# rxcalibrate.net
KiCad netlist of a schematic drawn in Altium Designer
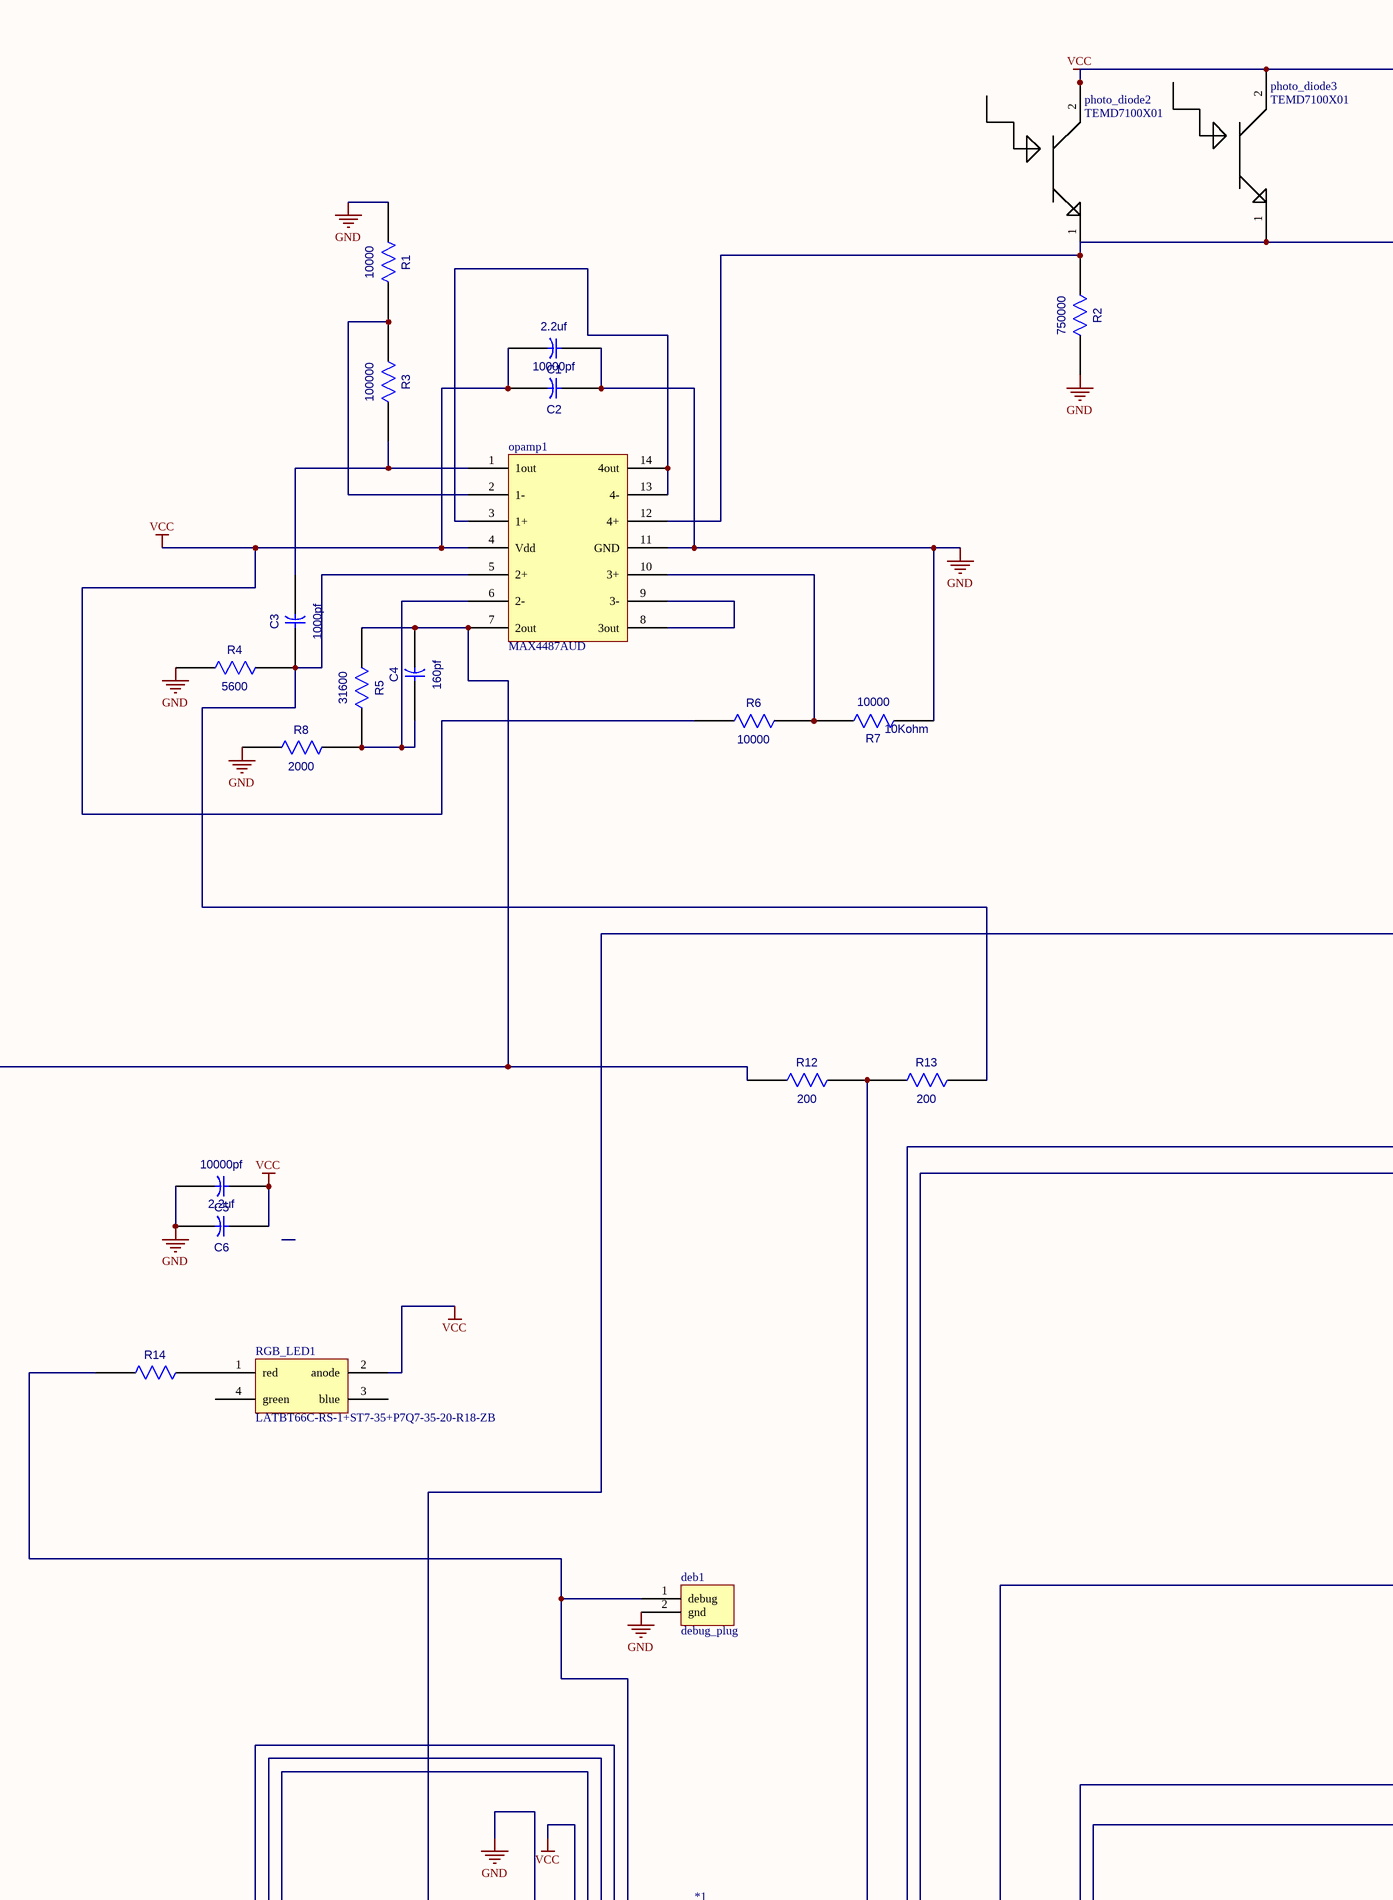
[diagram p0: rxcalibrate.SchDoc, top left]
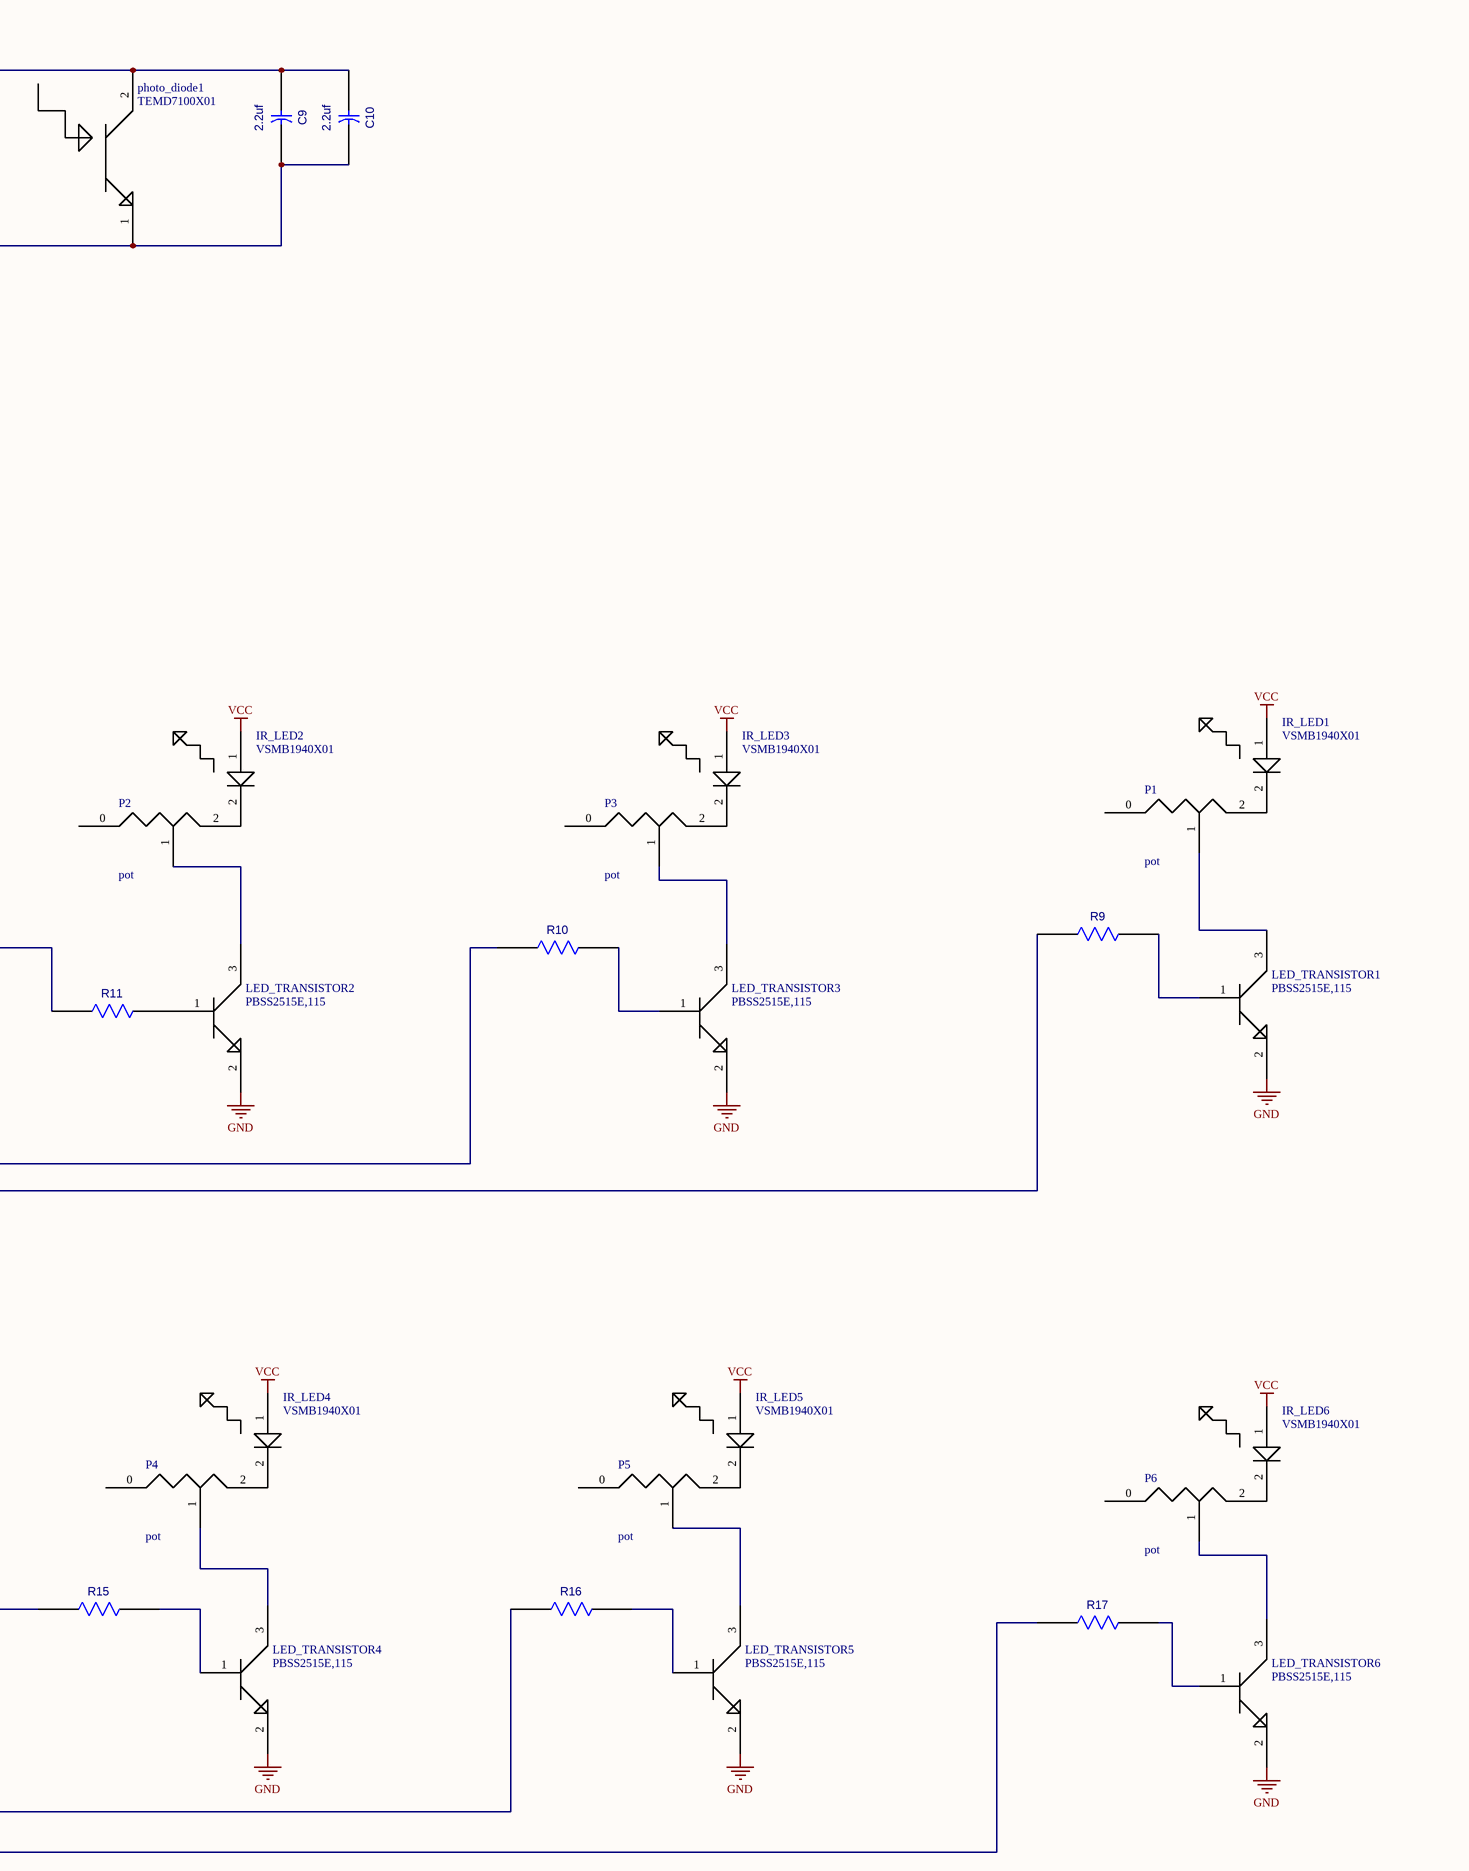
[diagram p1: rxcalibrate.SchDoc, top right]
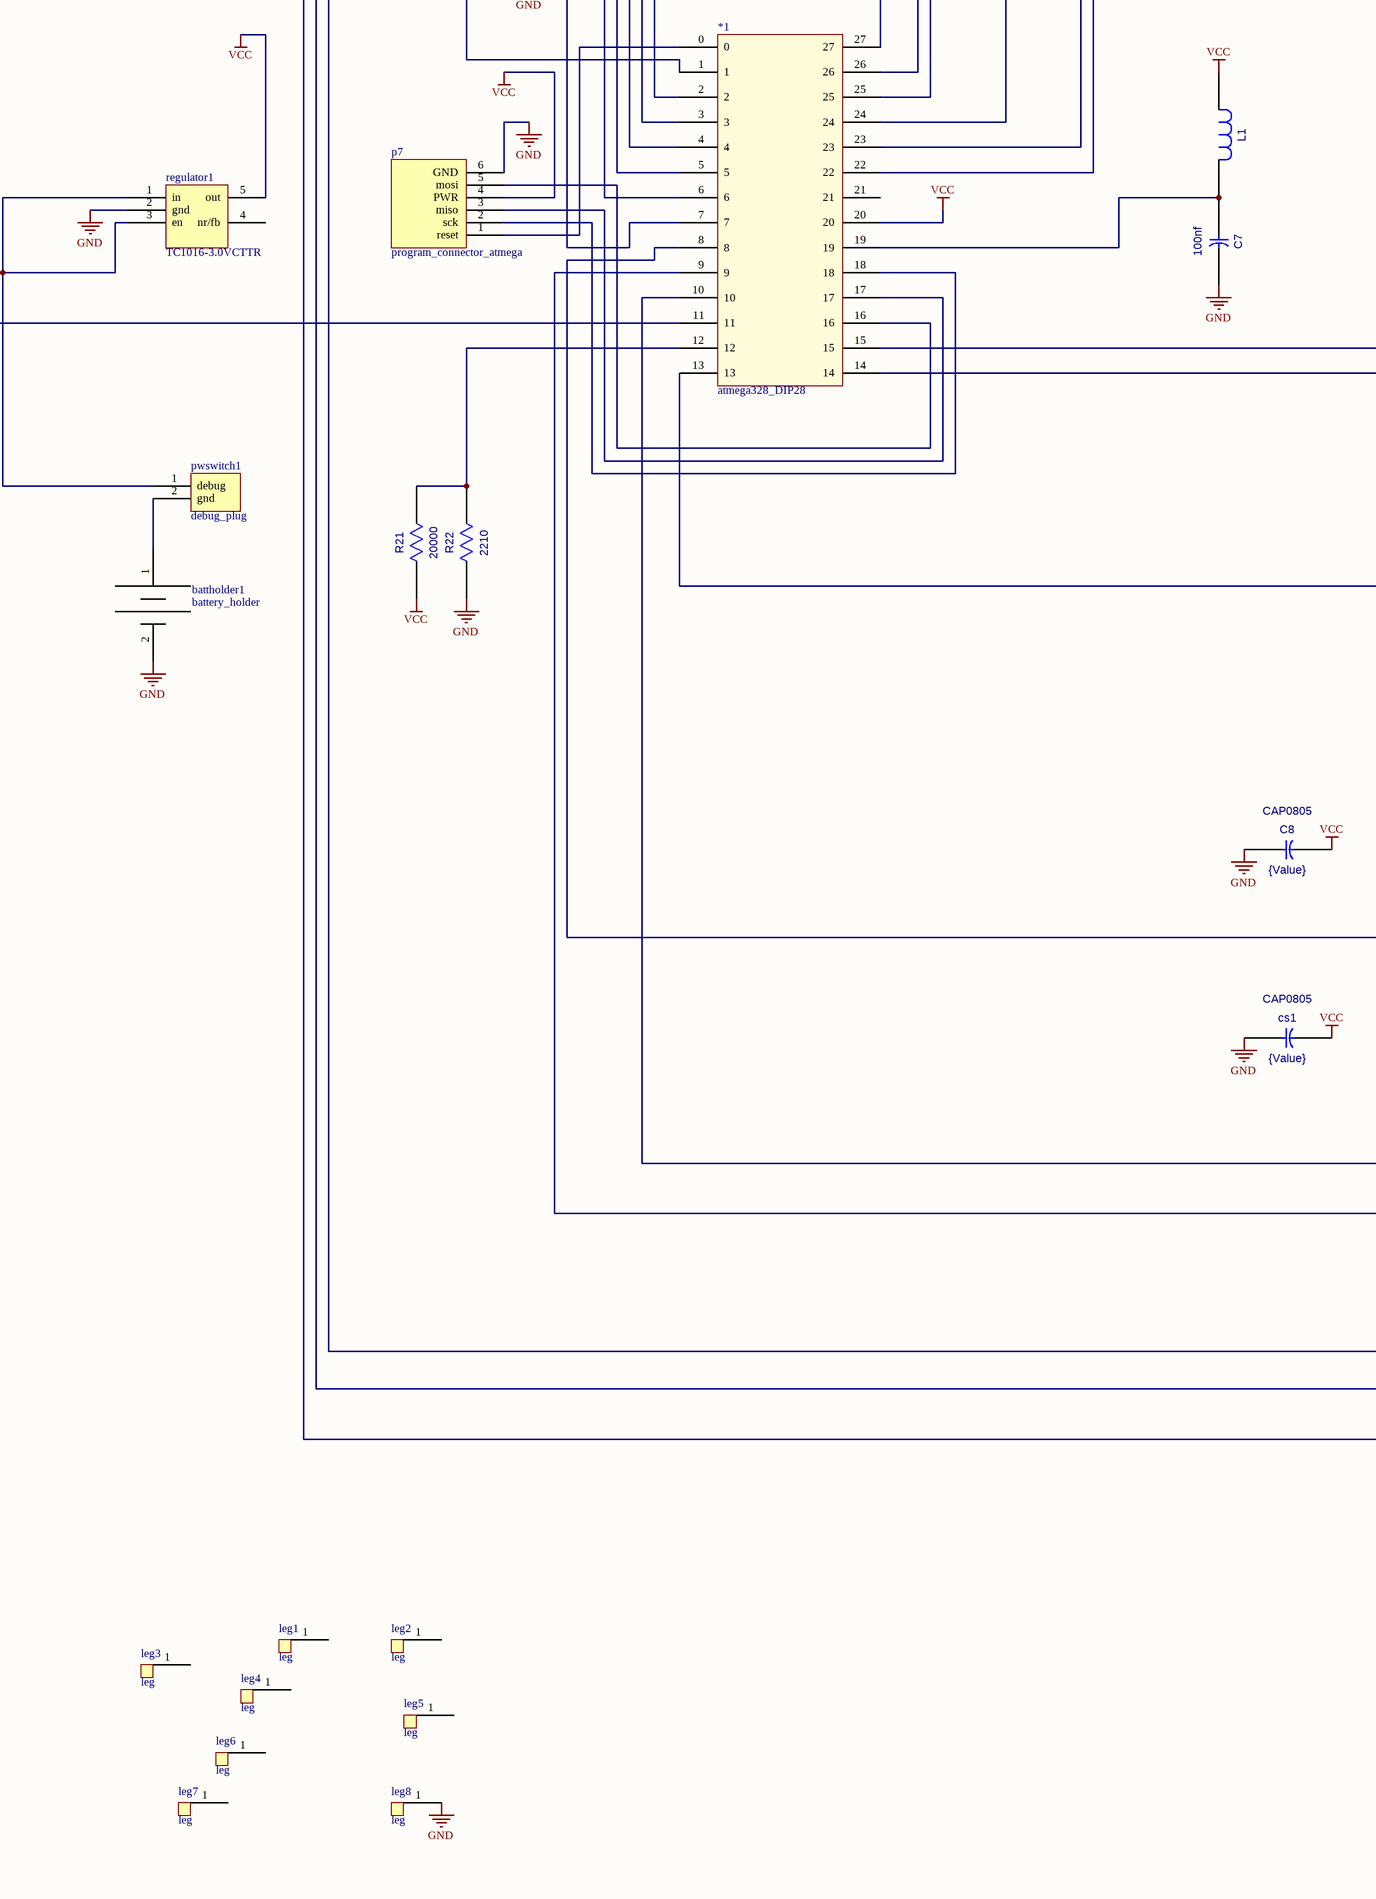
[diagram p2: rxcalibrate.SchDoc, bottom left]
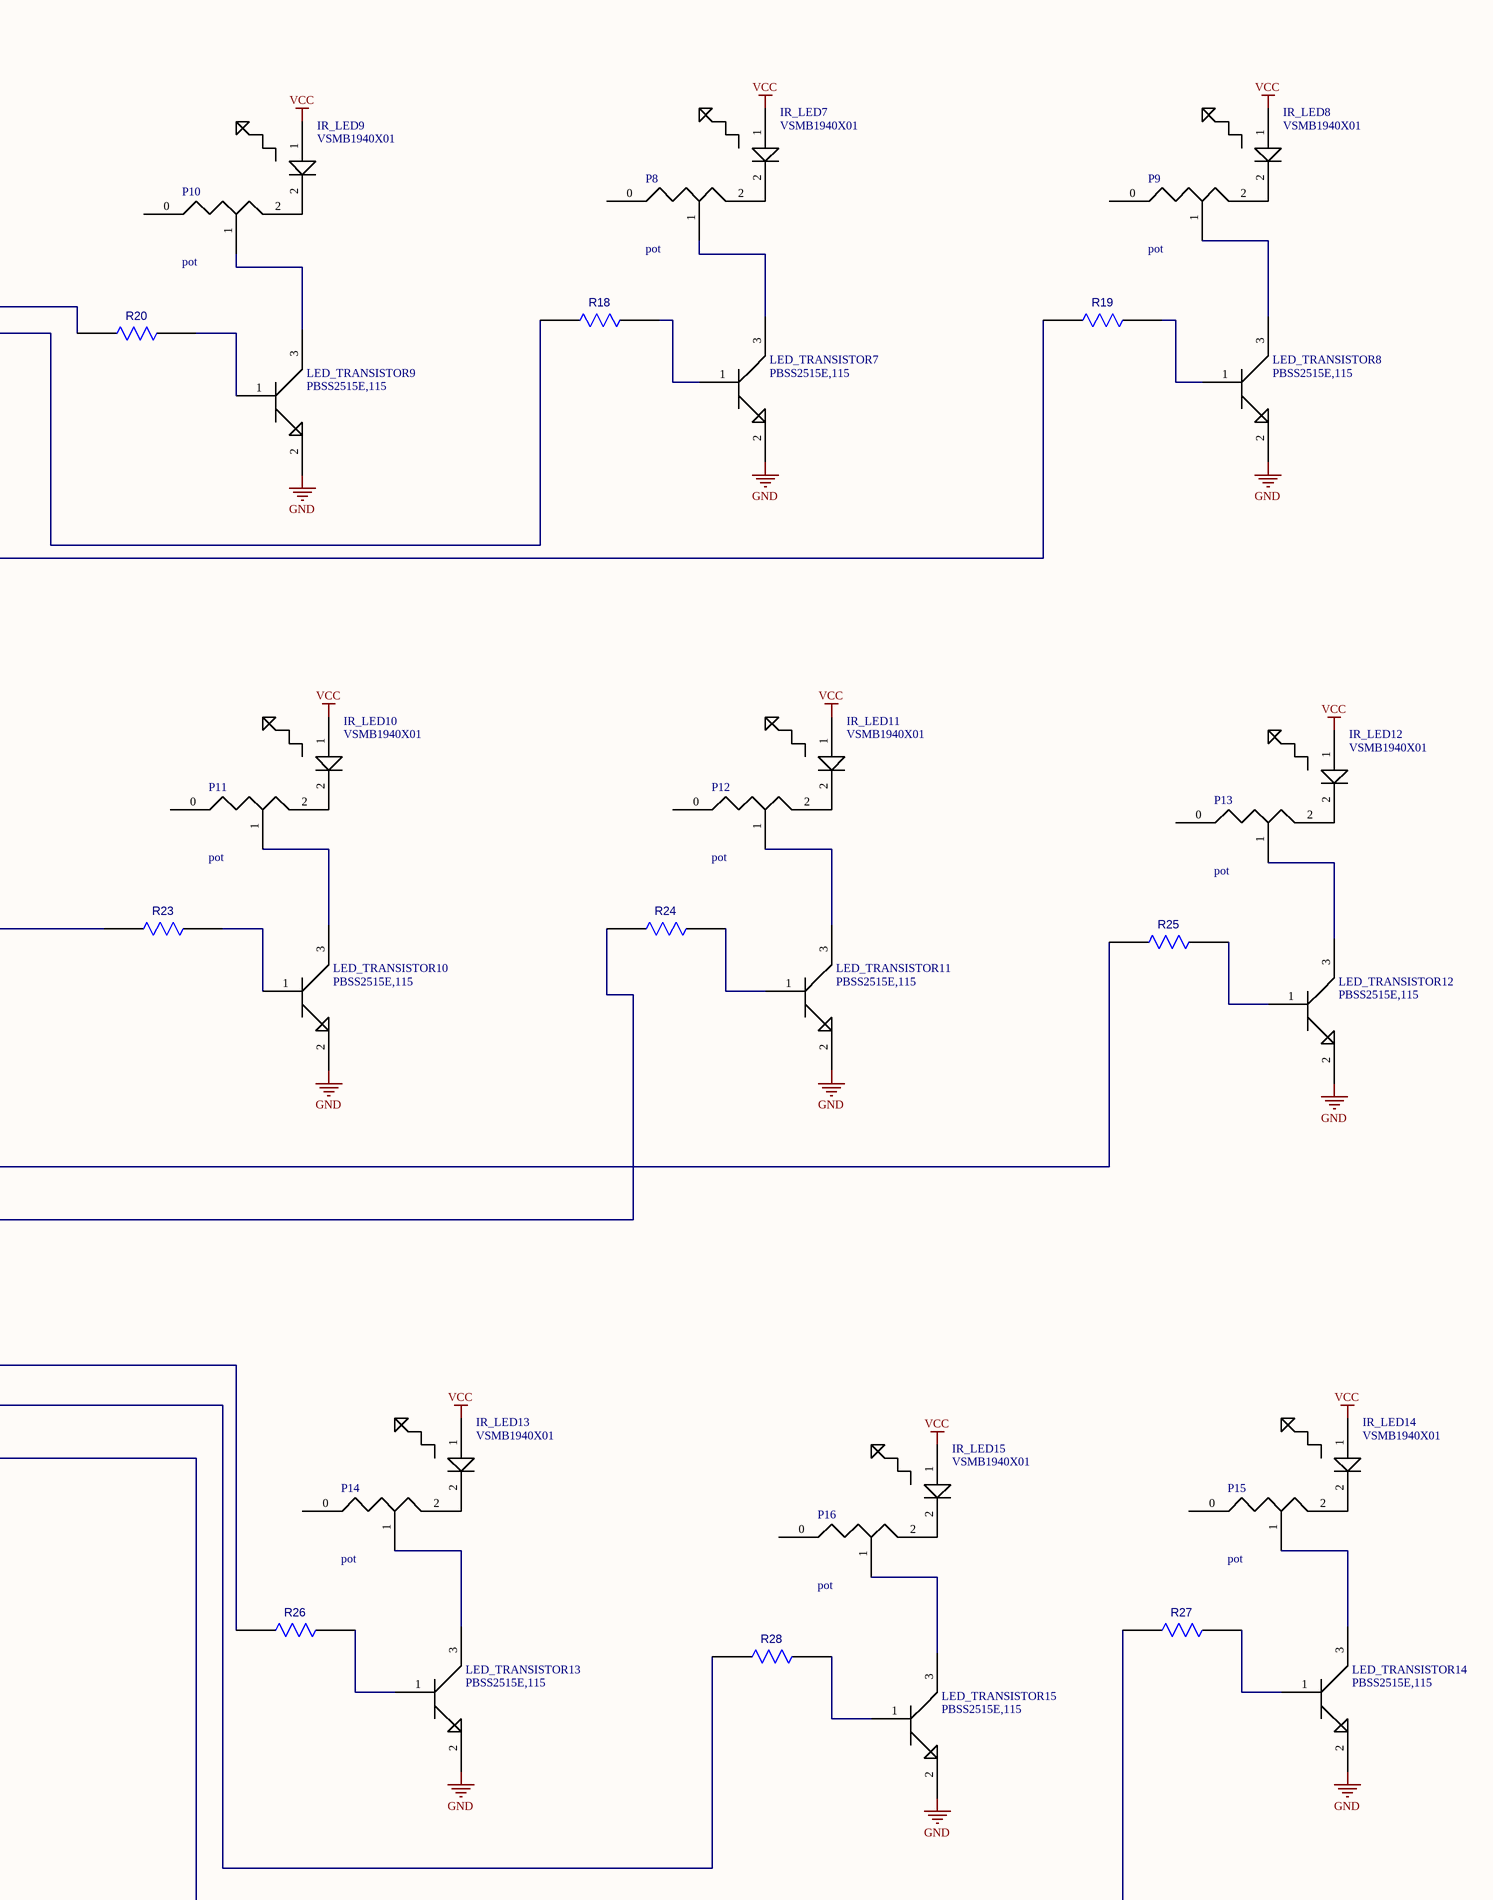
[diagram p3: rxcalibrate.SchDoc, bottom right]

(export (version "E")
  (design (tool "Eeschema 10.0.6"))
  (components
    (comp (ref "*1")
      (value "atmega328_DIP28")
      (footprint "atmega328dip")
      (libsource (lib "JMAC.~(21)") (part "atmega328_DIP28"))
    )
    (comp (ref "battholder1")
      (value "battery_holder")
      (footprint "Battery_mount")
      (libsource (lib "JMAC.~(21)") (part "battery_holder"))
    )
    (comp (ref "C1")
      (value "2.2uf")
      (footprint "RC0603")
      (description "CAP0603")
      (fields (field (name "ALTIUM_UNNAMED_1") "2.2uf"))
      (libsource (lib "JMAC") (part "CAP0603"))
    )
    (comp (ref "C2")
      (value "10000pf")
      (footprint "RC0603")
      (description "CAP0603")
      (fields (field (name "ALTIUM_UNNAMED_1") "10000pf"))
      (libsource (lib "JMAC") (part "CAP0603"))
    )
    (comp (ref "C3")
      (value "1000pf")
      (footprint "RC0603")
      (description "CAP0603")
      (fields (field (name "ALTIUM_UNNAMED_1") "1000pf"))
      (libsource (lib "JMAC") (part "CAP0603"))
    )
    (comp (ref "C4")
      (value "160pf")
      (footprint "RC0603")
      (description "CAP0603")
      (fields (field (name "ALTIUM_UNNAMED_1") "160pf"))
      (libsource (lib "JMAC") (part "CAP0603"))
    )
    (comp (ref "C5")
      (value "10000pf")
      (footprint "RC0603")
      (description "CAP0603")
      (fields (field (name "ALTIUM_UNNAMED_1") "10000pf"))
      (libsource (lib "JMAC") (part "CAP0603"))
    )
    (comp (ref "C6")
      (value "2.2uf")
      (footprint "RC0603")
      (description "CAP0603")
      (fields (field (name "ALTIUM_UNNAMED_1") "2.2uf"))
      (libsource (lib "JMAC") (part "CAP0603"))
    )
    (comp (ref "C7")
      (value "100nf")
      (footprint "RC0603")
      (description "CAP0603")
      (fields (field (name "ALTIUM_UNNAMED_1") "100nf"))
      (libsource (lib "JMAC") (part "CAP0603"))
    )
    (comp (ref "C8")
      (value "CAP0805")
      (footprint "RC0805_CAP0805(Primary)")
      (fields (field (name "ALTIUM_VALUE") "{Value}"))
      (libsource (lib "JMAC.~(21)") (part "CAP0805"))
    )
    (comp (ref "C9")
      (value "2.2uf")
      (footprint "RC0603")
      (description "CAP0603")
      (fields (field (name "ALTIUM_UNNAMED_1") "2.2uf"))
      (libsource (lib "JMAC") (part "CAP0603"))
    )
    (comp (ref "C10")
      (value "2.2uf")
      (footprint "RC0603")
      (description "CAP0603")
      (fields (field (name "ALTIUM_UNNAMED_1") "2.2uf"))
      (libsource (lib "JMAC") (part "CAP0603"))
    )
    (comp (ref "cs1")
      (value "CAP0805")
      (footprint "RC0805_CAP0805(Primary)")
      (fields (field (name "ALTIUM_VALUE") "{Value}"))
      (libsource (lib "JMAC.~(21)") (part "CAP0805"))
    )
    (comp (ref "deb1")
      (value "debug_plug")
      (footprint "debug_conn")
      (libsource (lib "JMAC.~(21)") (part "debug_plug"))
    )
    (comp (ref "IR_LED1")
      (value "VSMB1940X01")
      (footprint "0805")
      (libsource (lib "JMAC.~(21)") (part "IRtx"))
    )
    (comp (ref "IR_LED2")
      (value "VSMB1940X01")
      (footprint "0805")
      (libsource (lib "JMAC.~(21)") (part "IRtx"))
    )
    (comp (ref "IR_LED3")
      (value "VSMB1940X01")
      (footprint "0805")
      (libsource (lib "JMAC.~(21)") (part "IRtx"))
    )
    (comp (ref "IR_LED4")
      (value "VSMB1940X01")
      (footprint "0805")
      (libsource (lib "JMAC.~(21)") (part "IRtx"))
    )
    (comp (ref "IR_LED5")
      (value "VSMB1940X01")
      (footprint "0805")
      (libsource (lib "JMAC.~(21)") (part "IRtx"))
    )
    (comp (ref "IR_LED6")
      (value "VSMB1940X01")
      (footprint "0805")
      (libsource (lib "JMAC.~(21)") (part "IRtx"))
    )
    (comp (ref "IR_LED7")
      (value "VSMB1940X01")
      (footprint "0805")
      (libsource (lib "JMAC.~(21)") (part "IRtx"))
    )
    (comp (ref "IR_LED8")
      (value "VSMB1940X01")
      (footprint "0805")
      (libsource (lib "JMAC.~(21)") (part "IRtx"))
    )
    (comp (ref "IR_LED9")
      (value "VSMB1940X01")
      (footprint "0805")
      (libsource (lib "JMAC.~(21)") (part "IRtx"))
    )
    (comp (ref "IR_LED10")
      (value "VSMB1940X01")
      (footprint "0805")
      (libsource (lib "JMAC.~(21)") (part "IRtx"))
    )
    (comp (ref "IR_LED11")
      (value "VSMB1940X01")
      (footprint "0805")
      (libsource (lib "JMAC.~(21)") (part "IRtx"))
    )
    (comp (ref "IR_LED12")
      (value "VSMB1940X01")
      (footprint "0805")
      (libsource (lib "JMAC.~(21)") (part "IRtx"))
    )
    (comp (ref "IR_LED13")
      (value "VSMB1940X01")
      (footprint "0805")
      (libsource (lib "JMAC.~(21)") (part "IRtx"))
    )
    (comp (ref "IR_LED14")
      (value "VSMB1940X01")
      (footprint "0805")
      (libsource (lib "JMAC.~(21)") (part "IRtx"))
    )
    (comp (ref "IR_LED15")
      (value "VSMB1940X01")
      (footprint "0805")
      (libsource (lib "JMAC.~(21)") (part "IRtx"))
    )
    (comp (ref "L1")
      (value "LQM18FN100M00D")
      (footprint "RC0603")
      (description "IND0603")
      (libsource (lib "JMAC.~(21)") (part "IND0603"))
    )
    (comp (ref "LED_TRANSISTOR1")
      (value "PBSS2515E,115")
      (footprint "sot416")
      (libsource (lib "JMAC.~(21)") (part "transistor_led"))
    )
    (comp (ref "LED_TRANSISTOR2")
      (value "PBSS2515E,115")
      (footprint "sot416")
      (libsource (lib "JMAC.~(21)") (part "transistor_led"))
    )
    (comp (ref "LED_TRANSISTOR3")
      (value "PBSS2515E,115")
      (footprint "sot416")
      (libsource (lib "JMAC.~(21)") (part "transistor_led"))
    )
    (comp (ref "LED_TRANSISTOR4")
      (value "PBSS2515E,115")
      (footprint "sot416")
      (libsource (lib "JMAC.~(21)") (part "transistor_led"))
    )
    (comp (ref "LED_TRANSISTOR5")
      (value "PBSS2515E,115")
      (footprint "sot416")
      (libsource (lib "JMAC.~(21)") (part "transistor_led"))
    )
    (comp (ref "LED_TRANSISTOR6")
      (value "PBSS2515E,115")
      (footprint "sot416")
      (libsource (lib "JMAC.~(21)") (part "transistor_led"))
    )
    (comp (ref "LED_TRANSISTOR7")
      (value "PBSS2515E,115")
      (footprint "sot416")
      (libsource (lib "JMAC.~(21)") (part "transistor_led"))
    )
    (comp (ref "LED_TRANSISTOR8")
      (value "PBSS2515E,115")
      (footprint "sot416")
      (libsource (lib "JMAC.~(21)") (part "transistor_led"))
    )
    (comp (ref "LED_TRANSISTOR9")
      (value "PBSS2515E,115")
      (footprint "sot416")
      (libsource (lib "JMAC.~(21)") (part "transistor_led"))
    )
    (comp (ref "LED_TRANSISTOR10")
      (value "PBSS2515E,115")
      (footprint "sot416")
      (libsource (lib "JMAC.~(21)") (part "transistor_led"))
    )
    (comp (ref "LED_TRANSISTOR11")
      (value "PBSS2515E,115")
      (footprint "sot416")
      (libsource (lib "JMAC.~(21)") (part "transistor_led"))
    )
    (comp (ref "LED_TRANSISTOR12")
      (value "PBSS2515E,115")
      (footprint "sot416")
      (libsource (lib "JMAC.~(21)") (part "transistor_led"))
    )
    (comp (ref "LED_TRANSISTOR13")
      (value "PBSS2515E,115")
      (footprint "sot416")
      (libsource (lib "JMAC.~(21)") (part "transistor_led"))
    )
    (comp (ref "LED_TRANSISTOR14")
      (value "PBSS2515E,115")
      (footprint "sot416")
      (libsource (lib "JMAC.~(21)") (part "transistor_led"))
    )
    (comp (ref "LED_TRANSISTOR15")
      (value "PBSS2515E,115")
      (footprint "sot416")
      (libsource (lib "JMAC.~(21)") (part "transistor_led"))
    )
    (comp (ref "leg1") (value "leg") (footprint "leg") (libsource (lib "JMAC.~(21)") (part "leg")))
    (comp (ref "leg2") (value "leg") (footprint "leg") (libsource (lib "JMAC.~(21)") (part "leg")))
    (comp (ref "leg3") (value "leg") (footprint "leg") (libsource (lib "JMAC.~(21)") (part "leg")))
    (comp (ref "leg4") (value "leg") (footprint "leg") (libsource (lib "JMAC.~(21)") (part "leg")))
    (comp (ref "leg5") (value "leg") (footprint "leg") (libsource (lib "JMAC.~(21)") (part "leg")))
    (comp (ref "leg6") (value "leg") (footprint "leg") (libsource (lib "JMAC.~(21)") (part "leg")))
    (comp (ref "leg7") (value "leg") (footprint "leg") (libsource (lib "JMAC.~(21)") (part "leg")))
    (comp (ref "leg8") (value "leg") (footprint "leg") (libsource (lib "JMAC.~(21)") (part "leg")))
    (comp (ref "opamp1")
      (value "MAX4487AUD")
      (footprint "TSSOP14")
      (libsource (lib "JMAC.~(21)") (part "opamp"))
    )
    (comp (ref "P1") (value "pot") (footprint "POT_PV36W") (libsource (lib "JMAC.~(21)") (part "pot")))
    (comp (ref "P2") (value "pot") (footprint "POT_PV36W") (libsource (lib "JMAC.~(21)") (part "pot")))
    (comp (ref "P3") (value "pot") (footprint "POT_PV36W") (libsource (lib "JMAC.~(21)") (part "pot")))
    (comp (ref "P4") (value "pot") (footprint "POT_PV36W") (libsource (lib "JMAC.~(21)") (part "pot")))
    (comp (ref "P5") (value "pot") (footprint "POT_PV36W") (libsource (lib "JMAC.~(21)") (part "pot")))
    (comp (ref "P6") (value "pot") (footprint "POT_PV36W") (libsource (lib "JMAC.~(21)") (part "pot")))
    (comp (ref "p7")
      (value "program_connector_atmega")
      (footprint "Programming_connector")
      (libsource (lib "JMAC.~(21)") (part "program_connector_atmega"))
    )
    (comp (ref "P8") (value "pot") (footprint "POT_PV36W") (libsource (lib "JMAC.~(21)") (part "pot")))
    (comp (ref "P9") (value "pot") (footprint "POT_PV36W") (libsource (lib "JMAC.~(21)") (part "pot")))
    (comp (ref "P10") (value "pot") (footprint "POT_PV36W") (libsource (lib "JMAC.~(21)") (part "pot")))
    (comp (ref "P11") (value "pot") (footprint "POT_PV36W") (libsource (lib "JMAC.~(21)") (part "pot")))
    (comp (ref "P12") (value "pot") (footprint "POT_PV36W") (libsource (lib "JMAC.~(21)") (part "pot")))
    (comp (ref "P13") (value "pot") (footprint "POT_PV36W") (libsource (lib "JMAC.~(21)") (part "pot")))
    (comp (ref "P14") (value "pot") (footprint "POT_PV36W") (libsource (lib "JMAC.~(21)") (part "pot")))
    (comp (ref "P15") (value "pot") (footprint "POT_PV36W") (libsource (lib "JMAC.~(21)") (part "pot")))
    (comp (ref "P16") (value "pot") (footprint "POT_PV36W") (libsource (lib "JMAC.~(21)") (part "pot")))
    (comp (ref "photo_diode1")
      (value "TEMD7100X01")
      (footprint "0805")
      (libsource (lib "JMAC.~(21)") (part "IRrx"))
    )
    (comp (ref "photo_diode2")
      (value "TEMD7100X01")
      (footprint "0805")
      (libsource (lib "JMAC.~(21)") (part "IRrx"))
    )
    (comp (ref "photo_diode3")
      (value "TEMD7100X01")
      (footprint "0805")
      (libsource (lib "JMAC.~(21)") (part "IRrx"))
    )
    (comp (ref "pwswitch1")
      (value "debug_plug")
      (footprint "debug_conn")
      (libsource (lib "JMAC.~(21)") (part "debug_plug"))
    )
    (comp (ref "R1")
      (value "10 Kohm")
      (footprint "RC0603")
      (description "RES0603 10Kohm")
      (fields (field (name "ALTIUM_UNNAMED_1") "10000"))
      (libsource (lib "JMAC") (part "RES0603"))
    )
    (comp (ref "R2")
      (value "750 K ohm")
      (footprint "RC0603")
      (description "RES0603 750000 ohm")
      (fields (field (name "ALTIUM_UNNAMED_1") "750000"))
      (libsource (lib "JMAC") (part "RES0603"))
    )
    (comp (ref "R3")
      (value "100Kohm")
      (footprint "RC0603")
      (description "RES0603 100Kohm")
      (fields (field (name "ALTIUM_UNNAMED_1") "100000"))
      (libsource (lib "JMAC") (part "RES0603"))
    )
    (comp (ref "R4")
      (value "5600 ohm")
      (footprint "RC0603")
      (description "RES0603 5600 ohm")
      (fields (field (name "ALTIUM_UNNAMED_1") "5600"))
      (libsource (lib "JMAC") (part "RES0603"))
    )
    (comp (ref "R5")
      (value "31.6Kohm")
      (footprint "RC0603")
      (description "RES0603 31.6Kohm")
      (fields (field (name "ALTIUM_UNNAMED_1") "31600"))
      (libsource (lib "JMAC") (part "RES0603"))
    )
    (comp (ref "R6")
      (value "10Kohm")
      (footprint "RC0603")
      (description "RES0603 10Kohm")
      (fields (field (name "ALTIUM_UNNAMED_1") "10000"))
      (libsource (lib "JMAC") (part "RES0603"))
    )
    (comp (ref "R7")
      (value "10Kohm")
      (footprint "RC0603")
      (description "RES0603 10Kohm")
      (fields (field (name "ALTIUM_UNNAMED_1") "10000"))
      (libsource (lib "JMAC") (part "RES0603"))
    )
    (comp (ref "R8")
      (value "2Kohm")
      (footprint "RC0603")
      (description "RES0603 2Kohm")
      (fields (field (name "ALTIUM_UNNAMED_1") "2000"))
      (libsource (lib "JMAC") (part "RES0603"))
    )
    (comp (ref "R9") (value "RES0603") (footprint "RC0603") (libsource (lib "JMAC.~(21)") (part "RES0603")))
    (comp (ref "R10") (value "RES0603") (footprint "RC0603") (libsource (lib "JMAC.~(21)") (part "RES0603")))
    (comp (ref "R11") (value "RES0603") (footprint "RC0603") (libsource (lib "JMAC.~(21)") (part "RES0603")))
    (comp (ref "R12")
      (value "200 ohm")
      (footprint "RC0603")
      (description "RES0603 200 ohm")
      (fields (field (name "ALTIUM_UNNAMED_1") "200"))
      (libsource (lib "JMAC") (part "RES0603"))
    )
    (comp (ref "R13")
      (value "200 ohm")
      (footprint "RC0603")
      (description "RES0603 200 ohm")
      (fields (field (name "ALTIUM_UNNAMED_1") "200"))
      (libsource (lib "JMAC") (part "RES0603"))
    )
    (comp (ref "R14") (value "RES0603") (footprint "RC0603") (libsource (lib "JMAC.~(21)") (part "RES0603")))
    (comp (ref "R15") (value "RES0603") (footprint "RC0603") (libsource (lib "JMAC.~(21)") (part "RES0603")))
    (comp (ref "R16") (value "RES0603") (footprint "RC0603") (libsource (lib "JMAC.~(21)") (part "RES0603")))
    (comp (ref "R17") (value "RES0603") (footprint "RC0603") (libsource (lib "JMAC.~(21)") (part "RES0603")))
    (comp (ref "R18") (value "RES0603") (footprint "RC0603") (libsource (lib "JMAC.~(21)") (part "RES0603")))
    (comp (ref "R19") (value "RES0603") (footprint "RC0603") (libsource (lib "JMAC.~(21)") (part "RES0603")))
    (comp (ref "R20") (value "RES0603") (footprint "RC0603") (libsource (lib "JMAC.~(21)") (part "RES0603")))
    (comp (ref "R21")
      (value "20Kohm")
      (footprint "RC0603")
      (description "RES0603 20Kohm")
      (fields (field (name "ALTIUM_UNNAMED_1") "20000"))
      (libsource (lib "JMAC") (part "RES0603"))
    )
    (comp (ref "R22")
      (value "2210 ohm")
      (footprint "RC0603")
      (description "RES0603 2210 ohm")
      (fields (field (name "ALTIUM_UNNAMED_1") "2210"))
      (libsource (lib "JMAC") (part "RES0603"))
    )
    (comp (ref "R23") (value "RES0603") (footprint "RC0603") (libsource (lib "JMAC.~(21)") (part "RES0603")))
    (comp (ref "R24") (value "RES0603") (footprint "RC0603") (libsource (lib "JMAC.~(21)") (part "RES0603")))
    (comp (ref "R25") (value "RES0603") (footprint "RC0603") (libsource (lib "JMAC.~(21)") (part "RES0603")))
    (comp (ref "R26") (value "RES0603") (footprint "RC0603") (libsource (lib "JMAC.~(21)") (part "RES0603")))
    (comp (ref "R27") (value "RES0603") (footprint "RC0603") (libsource (lib "JMAC.~(21)") (part "RES0603")))
    (comp (ref "R28") (value "RES0603") (footprint "RC0603") (libsource (lib "JMAC.~(21)") (part "RES0603")))
    (comp (ref "regulator1")
      (value "TC1016-3.0VCTTR")
      (footprint "SOT23-5")
      (libsource (lib "JMAC.~(21)") (part "regulator_w_switch"))
    )
    (comp (ref "RGB_LED1")
      (value "LATBT66C-RS-1+ST7-35+P7Q7-35-20-R18-ZB")
      (footprint "rgb_led")
      (libsource (lib "JMAC.~(21)") (part "rgb_led"))
    )
  )
  (nets
    (net (code "1") (name "GND") (class "Default")
      (node (ref "*1") (pin "7") (pinfunction "7_7") (pintype "passive"))
      (node (ref "C1") (pin "2") (pintype "passive"))
      (node (ref "C2") (pin "2") (pintype "passive"))
      (node (ref "C5") (pin "1") (pintype "passive"))
      (node (ref "C6") (pin "1") (pintype "passive"))
      (node (ref "C7") (pin "1") (pintype "passive"))
      (node (ref "C8") (pin "A") (pinfunction "A_A") (pintype "passive"))
      (node (ref "LED_TRANSISTOR1") (pin "2") (pinfunction "out_2") (pintype "passive"))
      (node (ref "LED_TRANSISTOR10") (pin "2") (pinfunction "out_2") (pintype "passive"))
      (node (ref "LED_TRANSISTOR11") (pin "2") (pinfunction "out_2") (pintype "passive"))
      (node (ref "LED_TRANSISTOR12") (pin "2") (pinfunction "out_2") (pintype "passive"))
      (node (ref "LED_TRANSISTOR13") (pin "2") (pinfunction "out_2") (pintype "passive"))
      (node (ref "LED_TRANSISTOR14") (pin "2") (pinfunction "out_2") (pintype "passive"))
      (node (ref "LED_TRANSISTOR15") (pin "2") (pinfunction "out_2") (pintype "passive"))
      (node (ref "LED_TRANSISTOR2") (pin "2") (pinfunction "out_2") (pintype "passive"))
      (node (ref "LED_TRANSISTOR3") (pin "2") (pinfunction "out_2") (pintype "passive"))
      (node (ref "LED_TRANSISTOR4") (pin "2") (pinfunction "out_2") (pintype "passive"))
      (node (ref "LED_TRANSISTOR5") (pin "2") (pinfunction "out_2") (pintype "passive"))
      (node (ref "LED_TRANSISTOR6") (pin "2") (pinfunction "out_2") (pintype "passive"))
      (node (ref "LED_TRANSISTOR7") (pin "2") (pinfunction "out_2") (pintype "passive"))
      (node (ref "LED_TRANSISTOR8") (pin "2") (pinfunction "out_2") (pintype "passive"))
      (node (ref "LED_TRANSISTOR9") (pin "2") (pinfunction "out_2") (pintype "passive"))
      (node (ref "R1") (pin "2") (pinfunction "B_2") (pintype "passive"))
      (node (ref "R2") (pin "1") (pinfunction "A_1") (pintype "passive"))
      (node (ref "R22") (pin "2") (pinfunction "B_2") (pintype "passive"))
      (node (ref "R4") (pin "2") (pinfunction "B_2") (pintype "passive"))
      (node (ref "R7") (pin "2") (pinfunction "B_2") (pintype "passive"))
      (node (ref "R8") (pin "2") (pinfunction "B_2") (pintype "passive"))
      (node (ref "battholder1") (pin "2") (pintype "passive"))
      (node (ref "cs1") (pin "A") (pinfunction "A_A") (pintype "passive"))
      (node (ref "deb1") (pin "2") (pinfunction "gnd_2") (pintype "passive"))
      (node (ref "leg8") (pin "1") (pinfunction "out_1") (pintype "passive"))
      (node (ref "opamp1") (pin "11") (pinfunction "GND_11") (pintype "passive"))
      (node (ref "p7") (pin "6") (pinfunction "GND_6") (pintype "passive"))
      (node (ref "regulator1") (pin "2") (pinfunction "gnd_2") (pintype "passive"))
    )
    (net (code "2") (name "Net-(IR_LED1-Pad2)") (class "Default")
      (node (ref "IR_LED1") (pin "2") (pintype "passive"))
      (node (ref "P1") (pin "2") (pinfunction "2_2") (pintype "passive"))
    )
    (net (code "3") (name "Net-(IR_LED2-Pad2)") (class "Default")
      (node (ref "IR_LED2") (pin "2") (pintype "passive"))
      (node (ref "P2") (pin "2") (pinfunction "2_2") (pintype "passive"))
    )
    (net (code "4") (name "Net-(IR_LED3-Pad2)") (class "Default")
      (node (ref "IR_LED3") (pin "2") (pintype "passive"))
      (node (ref "P3") (pin "2") (pinfunction "2_2") (pintype "passive"))
    )
    (net (code "5") (name "Net-(IR_LED4-Pad2)") (class "Default")
      (node (ref "IR_LED4") (pin "2") (pintype "passive"))
      (node (ref "P4") (pin "2") (pinfunction "2_2") (pintype "passive"))
    )
    (net (code "6") (name "Net-(IR_LED5-Pad2)") (class "Default")
      (node (ref "IR_LED5") (pin "2") (pintype "passive"))
      (node (ref "P5") (pin "2") (pinfunction "2_2") (pintype "passive"))
    )
    (net (code "7") (name "Net-(IR_LED6-Pad2)") (class "Default")
      (node (ref "IR_LED6") (pin "2") (pintype "passive"))
      (node (ref "P6") (pin "2") (pinfunction "2_2") (pintype "passive"))
    )
    (net (code "8") (name "Net-(IR_LED7-Pad2)") (class "Default")
      (node (ref "IR_LED7") (pin "2") (pintype "passive"))
      (node (ref "P8") (pin "2") (pinfunction "2_2") (pintype "passive"))
    )
    (net (code "9") (name "Net-(IR_LED8-Pad2)") (class "Default")
      (node (ref "IR_LED8") (pin "2") (pintype "passive"))
      (node (ref "P9") (pin "2") (pinfunction "2_2") (pintype "passive"))
    )
    (net (code "10") (name "Net-(IR_LED9-Pad2)") (class "Default")
      (node (ref "IR_LED9") (pin "2") (pintype "passive"))
      (node (ref "P10") (pin "2") (pinfunction "2_2") (pintype "passive"))
    )
    (net (code "11") (name "Net-(IR_LED10-Pad2)") (class "Default")
      (node (ref "IR_LED10") (pin "2") (pintype "passive"))
      (node (ref "P11") (pin "2") (pinfunction "2_2") (pintype "passive"))
    )
    (net (code "12") (name "Net-(IR_LED11-Pad2)") (class "Default")
      (node (ref "IR_LED11") (pin "2") (pintype "passive"))
      (node (ref "P12") (pin "2") (pinfunction "2_2") (pintype "passive"))
    )
    (net (code "13") (name "Net-(IR_LED12-Pad2)") (class "Default")
      (node (ref "IR_LED12") (pin "2") (pintype "passive"))
      (node (ref "P13") (pin "2") (pinfunction "2_2") (pintype "passive"))
    )
    (net (code "14") (name "Net-(IR_LED13-Pad2)") (class "Default")
      (node (ref "IR_LED13") (pin "2") (pintype "passive"))
      (node (ref "P14") (pin "2") (pinfunction "2_2") (pintype "passive"))
    )
    (net (code "15") (name "Net-(IR_LED14-Pad2)") (class "Default")
      (node (ref "IR_LED14") (pin "2") (pintype "passive"))
      (node (ref "P15") (pin "2") (pinfunction "2_2") (pintype "passive"))
    )
    (net (code "16") (name "Net-(IR_LED15-Pad2)") (class "Default")
      (node (ref "IR_LED15") (pin "2") (pintype "passive"))
      (node (ref "P16") (pin "2") (pinfunction "2_2") (pintype "passive"))
    )
    (net (code "17") (name "Net-(L1-A)") (class "Default")
      (node (ref "*1") (pin "19") (pinfunction "19_19") (pintype "passive"))
      (node (ref "C7") (pin "2") (pintype "passive"))
      (node (ref "L1") (pin "2") (pinfunction "A_2") (pintype "passive"))
    )
    (net (code "18") (name "Net-(LED_TRANSISTOR1-Pad3)") (class "Default")
      (node (ref "LED_TRANSISTOR1") (pin "3") (pinfunction "3_3") (pintype "passive"))
      (node (ref "P1") (pin "1") (pinfunction "1_1") (pintype "passive"))
    )
    (net (code "19") (name "Net-(LED_TRANSISTOR2-Pad3)") (class "Default")
      (node (ref "LED_TRANSISTOR2") (pin "3") (pinfunction "3_3") (pintype "passive"))
      (node (ref "P2") (pin "1") (pinfunction "1_1") (pintype "passive"))
    )
    (net (code "20") (name "Net-(LED_TRANSISTOR3-Pad3)") (class "Default")
      (node (ref "LED_TRANSISTOR3") (pin "3") (pinfunction "3_3") (pintype "passive"))
      (node (ref "P3") (pin "1") (pinfunction "1_1") (pintype "passive"))
    )
    (net (code "21") (name "Net-(LED_TRANSISTOR4-Pad3)") (class "Default")
      (node (ref "LED_TRANSISTOR4") (pin "3") (pinfunction "3_3") (pintype "passive"))
      (node (ref "P4") (pin "1") (pinfunction "1_1") (pintype "passive"))
    )
    (net (code "22") (name "Net-(LED_TRANSISTOR5-Pad3)") (class "Default")
      (node (ref "LED_TRANSISTOR5") (pin "3") (pinfunction "3_3") (pintype "passive"))
      (node (ref "P5") (pin "1") (pinfunction "1_1") (pintype "passive"))
    )
    (net (code "23") (name "Net-(LED_TRANSISTOR6-Pad3)") (class "Default")
      (node (ref "LED_TRANSISTOR6") (pin "3") (pinfunction "3_3") (pintype "passive"))
      (node (ref "P6") (pin "1") (pinfunction "1_1") (pintype "passive"))
    )
    (net (code "24") (name "Net-(LED_TRANSISTOR7-Pad3)") (class "Default")
      (node (ref "LED_TRANSISTOR7") (pin "3") (pinfunction "3_3") (pintype "passive"))
      (node (ref "P8") (pin "1") (pinfunction "1_1") (pintype "passive"))
    )
    (net (code "25") (name "Net-(LED_TRANSISTOR8-Pad3)") (class "Default")
      (node (ref "LED_TRANSISTOR8") (pin "3") (pinfunction "3_3") (pintype "passive"))
      (node (ref "P9") (pin "1") (pinfunction "1_1") (pintype "passive"))
    )
    (net (code "26") (name "Net-(LED_TRANSISTOR9-Pad3)") (class "Default")
      (node (ref "LED_TRANSISTOR9") (pin "3") (pinfunction "3_3") (pintype "passive"))
      (node (ref "P10") (pin "1") (pinfunction "1_1") (pintype "passive"))
    )
    (net (code "27") (name "Net-(LED_TRANSISTOR10-Pad3)") (class "Default")
      (node (ref "LED_TRANSISTOR10") (pin "3") (pinfunction "3_3") (pintype "passive"))
      (node (ref "P11") (pin "1") (pinfunction "1_1") (pintype "passive"))
    )
    (net (code "28") (name "Net-(LED_TRANSISTOR11-Pad3)") (class "Default")
      (node (ref "LED_TRANSISTOR11") (pin "3") (pinfunction "3_3") (pintype "passive"))
      (node (ref "P12") (pin "1") (pinfunction "1_1") (pintype "passive"))
    )
    (net (code "29") (name "Net-(LED_TRANSISTOR12-Pad3)") (class "Default")
      (node (ref "LED_TRANSISTOR12") (pin "3") (pinfunction "3_3") (pintype "passive"))
      (node (ref "P13") (pin "1") (pinfunction "1_1") (pintype "passive"))
    )
    (net (code "30") (name "Net-(LED_TRANSISTOR13-Pad3)") (class "Default")
      (node (ref "LED_TRANSISTOR13") (pin "3") (pinfunction "3_3") (pintype "passive"))
      (node (ref "P14") (pin "1") (pinfunction "1_1") (pintype "passive"))
    )
    (net (code "31") (name "Net-(LED_TRANSISTOR14-Pad3)") (class "Default")
      (node (ref "LED_TRANSISTOR14") (pin "3") (pinfunction "3_3") (pintype "passive"))
      (node (ref "P15") (pin "1") (pinfunction "1_1") (pintype "passive"))
    )
    (net (code "32") (name "Net-(LED_TRANSISTOR15-Pad3)") (class "Default")
      (node (ref "LED_TRANSISTOR15") (pin "3") (pinfunction "3_3") (pintype "passive"))
      (node (ref "P16") (pin "1") (pinfunction "1_1") (pintype "passive"))
    )
    (net (code "33") (name "Net-(R1-A)") (class "Default")
      (node (ref "R1") (pin "1") (pinfunction "A_1") (pintype "passive"))
      (node (ref "R3") (pin "2") (pinfunction "B_2") (pintype "passive"))
      (node (ref "opamp1") (pin "2") (pinfunction "1-_2") (pintype "passive"))
    )
    (net (code "34") (name "Net-(R2-B)") (class "Default")
      (node (ref "C10") (pin "1") (pintype "passive"))
      (node (ref "C9") (pin "1") (pintype "passive"))
      (node (ref "R2") (pin "2") (pinfunction "B_2") (pintype "passive"))
      (node (ref "opamp1") (pin "12") (pinfunction "4+_12") (pintype "passive"))
      (node (ref "photo_diode1") (pin "1") (pintype "passive"))
      (node (ref "photo_diode2") (pin "1") (pintype "passive"))
      (node (ref "photo_diode3") (pin "1") (pintype "passive"))
    )
    (net (code "35") (name "Net-(R3-A)") (class "Default")
      (node (ref "C3") (pin "1") (pintype "passive"))
      (node (ref "R3") (pin "1") (pinfunction "A_1") (pintype "passive"))
      (node (ref "opamp1") (pin "1") (pinfunction "1out_1") (pintype "passive"))
    )
    (net (code "36") (name "Net-(R5-A)") (class "Default")
      (node (ref "C4") (pin "2") (pintype "passive"))
      (node (ref "R5") (pin "1") (pinfunction "A_1") (pintype "passive"))
      (node (ref "R8") (pin "1") (pinfunction "A_1") (pintype "passive"))
      (node (ref "opamp1") (pin "6") (pinfunction "2-_6") (pintype "passive"))
    )
    (net (code "37") (name "Net-(R6-A)") (class "Default")
      (node (ref "R6") (pin "1") (pinfunction "A_1") (pintype "passive"))
      (node (ref "R7") (pin "1") (pinfunction "A_1") (pintype "passive"))
      (node (ref "opamp1") (pin "10") (pinfunction "3+_10") (pintype "passive"))
    )
    (net (code "38") (name "Net-(R9-A)") (class "Default")
      (node (ref "LED_TRANSISTOR1") (pin "1") (pinfunction "out_1") (pintype "passive"))
      (node (ref "R9") (pin "1") (pinfunction "A_1") (pintype "passive"))
    )
    (net (code "39") (name "Net-(R9-B)") (class "Default")
      (node (ref "*1") (pin "25") (pinfunction "25_25") (pintype "passive"))
      (node (ref "R9") (pin "2") (pinfunction "B_2") (pintype "passive"))
    )
    (net (code "40") (name "Net-(R10-A)") (class "Default")
      (node (ref "LED_TRANSISTOR3") (pin "1") (pinfunction "out_1") (pintype "passive"))
      (node (ref "R10") (pin "1") (pinfunction "A_1") (pintype "passive"))
    )
    (net (code "41") (name "Net-(R10-B)") (class "Default")
      (node (ref "*1") (pin "26") (pinfunction "26_26") (pintype "passive"))
      (node (ref "R10") (pin "2") (pinfunction "B_2") (pintype "passive"))
    )
    (net (code "42") (name "Net-(R11-A)") (class "Default")
      (node (ref "LED_TRANSISTOR2") (pin "1") (pinfunction "out_1") (pintype "passive"))
      (node (ref "R11") (pin "1") (pinfunction "A_1") (pintype "passive"))
    )
    (net (code "43") (name "Net-(R11-B)") (class "Default")
      (node (ref "*1") (pin "1") (pinfunction "1_1") (pintype "passive"))
      (node (ref "R11") (pin "2") (pinfunction "B_2") (pintype "passive"))
    )
    (net (code "44") (name "Net-(R12-A)") (class "Default")
      (node (ref "*1") (pin "27") (pinfunction "27_27") (pintype "passive"))
      (node (ref "R12") (pin "1") (pinfunction "A_1") (pintype "passive"))
      (node (ref "R13") (pin "2") (pinfunction "B_2") (pintype "passive"))
    )
    (net (code "45") (name "Net-(R12-B)") (class "Default")
      (node (ref "*1") (pin "11") (pinfunction "11_11") (pintype "passive"))
      (node (ref "C4") (pin "1") (pintype "passive"))
      (node (ref "R12") (pin "2") (pinfunction "B_2") (pintype "passive"))
      (node (ref "R5") (pin "2") (pinfunction "B_2") (pintype "passive"))
      (node (ref "opamp1") (pin "7") (pinfunction "2out_7") (pintype "passive"))
    )
    (net (code "46") (name "Net-(R13-A)") (class "Default")
      (node (ref "C3") (pin "2") (pintype "passive"))
      (node (ref "R13") (pin "1") (pinfunction "A_1") (pintype "passive"))
      (node (ref "R4") (pin "1") (pinfunction "A_1") (pintype "passive"))
      (node (ref "opamp1") (pin "5") (pinfunction "2+_5") (pintype "passive"))
    )
    (net (code "47") (name "Net-(R14-A)") (class "Default")
      (node (ref "R14") (pin "1") (pinfunction "A_1") (pintype "passive"))
      (node (ref "RGB_LED1") (pin "1") (pinfunction "red_1") (pintype "passive"))
    )
    (net (code "48") (name "Net-(R14-B)") (class "Default")
      (node (ref "*1") (pin "2") (pinfunction "2_2") (pintype "passive"))
      (node (ref "R14") (pin "2") (pinfunction "B_2") (pintype "passive"))
      (node (ref "deb1") (pin "1") (pinfunction "debug_1") (pintype "passive"))
    )
    (net (code "49") (name "Net-(R15-A)") (class "Default")
      (node (ref "LED_TRANSISTOR4") (pin "1") (pinfunction "out_1") (pintype "passive"))
      (node (ref "R15") (pin "1") (pinfunction "A_1") (pintype "passive"))
    )
    (net (code "50") (name "Net-(R15-B)") (class "Default")
      (node (ref "*1") (pin "24") (pinfunction "24_24") (pintype "passive"))
      (node (ref "R15") (pin "2") (pinfunction "B_2") (pintype "passive"))
    )
    (net (code "51") (name "Net-(R16-A)") (class "Default")
      (node (ref "LED_TRANSISTOR5") (pin "1") (pinfunction "out_1") (pintype "passive"))
      (node (ref "R16") (pin "1") (pinfunction "A_1") (pintype "passive"))
    )
    (net (code "52") (name "Net-(R16-B)") (class "Default")
      (node (ref "*1") (pin "23") (pinfunction "23_23") (pintype "passive"))
      (node (ref "R16") (pin "2") (pinfunction "B_2") (pintype "passive"))
    )
    (net (code "53") (name "Net-(R17-A)") (class "Default")
      (node (ref "LED_TRANSISTOR6") (pin "1") (pinfunction "out_1") (pintype "passive"))
      (node (ref "R17") (pin "1") (pinfunction "A_1") (pintype "passive"))
    )
    (net (code "54") (name "Net-(R17-B)") (class "Default")
      (node (ref "*1") (pin "22") (pinfunction "22_22") (pintype "passive"))
      (node (ref "R17") (pin "2") (pinfunction "B_2") (pintype "passive"))
    )
    (net (code "55") (name "Net-(R18-A)") (class "Default")
      (node (ref "LED_TRANSISTOR7") (pin "1") (pinfunction "out_1") (pintype "passive"))
      (node (ref "R18") (pin "1") (pinfunction "A_1") (pintype "passive"))
    )
    (net (code "56") (name "Net-(R18-B)") (class "Default")
      (node (ref "*1") (pin "14") (pinfunction "14_14") (pintype "passive"))
      (node (ref "R18") (pin "2") (pinfunction "B_2") (pintype "passive"))
    )
    (net (code "57") (name "Net-(R19-A)") (class "Default")
      (node (ref "LED_TRANSISTOR8") (pin "1") (pinfunction "out_1") (pintype "passive"))
      (node (ref "R19") (pin "1") (pinfunction "A_1") (pintype "passive"))
    )
    (net (code "58") (name "Net-(R19-B)") (class "Default")
      (node (ref "*1") (pin "13") (pinfunction "13_13") (pintype "passive"))
      (node (ref "R19") (pin "2") (pinfunction "B_2") (pintype "passive"))
    )
    (net (code "59") (name "Net-(R20-A)") (class "Default")
      (node (ref "LED_TRANSISTOR9") (pin "1") (pinfunction "out_1") (pintype "passive"))
      (node (ref "R20") (pin "1") (pinfunction "A_1") (pintype "passive"))
    )
    (net (code "60") (name "Net-(R20-B)") (class "Default")
      (node (ref "*1") (pin "15") (pinfunction "15_15") (pintype "passive"))
      (node (ref "R20") (pin "2") (pinfunction "B_2") (pintype "passive"))
    )
    (net (code "61") (name "Net-(R21-A)") (class "Default")
      (node (ref "*1") (pin "12") (pinfunction "12_12") (pintype "passive"))
      (node (ref "R21") (pin "1") (pinfunction "A_1") (pintype "passive"))
      (node (ref "R22") (pin "1") (pinfunction "A_1") (pintype "passive"))
    )
    (net (code "62") (name "Net-(R23-A)") (class "Default")
      (node (ref "LED_TRANSISTOR10") (pin "1") (pinfunction "out_1") (pintype "passive"))
      (node (ref "R23") (pin "1") (pinfunction "A_1") (pintype "passive"))
    )
    (net (code "63") (name "Net-(R23-B)") (class "Default")
      (node (ref "*1") (pin "8") (pinfunction "8_8") (pintype "passive"))
      (node (ref "R23") (pin "2") (pinfunction "B_2") (pintype "passive"))
    )
    (net (code "64") (name "Net-(R24-A)") (class "Default")
      (node (ref "LED_TRANSISTOR11") (pin "1") (pinfunction "out_1") (pintype "passive"))
      (node (ref "R24") (pin "1") (pinfunction "A_1") (pintype "passive"))
    )
    (net (code "65") (name "Net-(R24-B)") (class "Default")
      (node (ref "*1") (pin "9") (pinfunction "9_9") (pintype "passive"))
      (node (ref "R24") (pin "2") (pinfunction "B_2") (pintype "passive"))
    )
    (net (code "66") (name "Net-(R25-A)") (class "Default")
      (node (ref "LED_TRANSISTOR12") (pin "1") (pinfunction "out_1") (pintype "passive"))
      (node (ref "R25") (pin "1") (pinfunction "A_1") (pintype "passive"))
    )
    (net (code "67") (name "Net-(R25-B)") (class "Default")
      (node (ref "*1") (pin "10") (pinfunction "10_10") (pintype "passive"))
      (node (ref "R25") (pin "2") (pinfunction "B_2") (pintype "passive"))
    )
    (net (code "68") (name "Net-(R26-A)") (class "Default")
      (node (ref "LED_TRANSISTOR13") (pin "1") (pinfunction "out_1") (pintype "passive"))
      (node (ref "R26") (pin "1") (pinfunction "A_1") (pintype "passive"))
    )
    (net (code "69") (name "Net-(R26-B)") (class "Default")
      (node (ref "*1") (pin "5") (pinfunction "5_5") (pintype "passive"))
      (node (ref "R26") (pin "2") (pinfunction "B_2") (pintype "passive"))
    )
    (net (code "70") (name "Net-(R27-A)") (class "Default")
      (node (ref "LED_TRANSISTOR14") (pin "1") (pinfunction "out_1") (pintype "passive"))
      (node (ref "R27") (pin "1") (pinfunction "A_1") (pintype "passive"))
    )
    (net (code "71") (name "Net-(R27-B)") (class "Default")
      (node (ref "*1") (pin "3") (pinfunction "3_3") (pintype "passive"))
      (node (ref "R27") (pin "2") (pinfunction "B_2") (pintype "passive"))
    )
    (net (code "72") (name "Net-(R28-A)") (class "Default")
      (node (ref "LED_TRANSISTOR15") (pin "1") (pinfunction "out_1") (pintype "passive"))
      (node (ref "R28") (pin "1") (pinfunction "A_1") (pintype "passive"))
    )
    (net (code "73") (name "Net-(R28-B)") (class "Default")
      (node (ref "*1") (pin "4") (pinfunction "4_4") (pintype "passive"))
      (node (ref "R28") (pin "2") (pinfunction "B_2") (pintype "passive"))
    )
    (net (code "74") (name "Net-(opamp1-1+)") (class "Default")
      (node (ref "opamp1") (pin "13") (pinfunction "4-_13") (pintype "passive"))
      (node (ref "opamp1") (pin "14") (pinfunction "4out_14") (pintype "passive"))
      (node (ref "opamp1") (pin "3") (pinfunction "1+_3") (pintype "passive"))
    )
    (net (code "75") (name "Net-(opamp1-3-)") (class "Default")
      (node (ref "opamp1") (pin "8") (pinfunction "3out_8") (pintype "passive"))
      (node (ref "opamp1") (pin "9") (pinfunction "3-_9") (pintype "passive"))
    )
    (net (code "76") (name "Net-(p7-miso)") (class "Default")
      (node (ref "*1") (pin "17") (pinfunction "17_17") (pintype "passive"))
      (node (ref "p7") (pin "3") (pinfunction "miso_3") (pintype "passive"))
    )
    (net (code "77") (name "Net-(p7-mosi)") (class "Default")
      (node (ref "*1") (pin "16") (pinfunction "16_16") (pintype "passive"))
      (node (ref "p7") (pin "5") (pinfunction "mosi_5") (pintype "passive"))
    )
    (net (code "78") (name "Net-(p7-reset)") (class "Default")
      (node (ref "*1") (pin "0") (pinfunction "0_0") (pintype "passive"))
      (node (ref "p7") (pin "1") (pinfunction "reset_1") (pintype "passive"))
    )
    (net (code "79") (name "Net-(p7-sck)") (class "Default")
      (node (ref "*1") (pin "18") (pinfunction "18_18") (pintype "passive"))
      (node (ref "p7") (pin "2") (pinfunction "sck_2") (pintype "passive"))
    )
    (net (code "80") (name "Net-(pwswitch1-debug)") (class "Default")
      (node (ref "pwswitch1") (pin "1") (pinfunction "debug_1") (pintype "passive"))
      (node (ref "regulator1") (pin "1") (pinfunction "in_1") (pintype "passive"))
      (node (ref "regulator1") (pin "3") (pinfunction "en_3") (pintype "passive"))
    )
    (net (code "81") (name "Net-(pwswitch1-gnd)") (class "Default")
      (node (ref "battholder1") (pin "1") (pintype "passive"))
      (node (ref "pwswitch1") (pin "2") (pinfunction "gnd_2") (pintype "passive"))
    )
    (net (code "82") (name "VCC") (class "Default")
      (node (ref "*1") (pin "20") (pinfunction "20_20") (pintype "passive"))
      (node (ref "*1") (pin "6") (pinfunction "6_6") (pintype "passive"))
      (node (ref "C1") (pin "1") (pintype "passive"))
      (node (ref "C10") (pin "2") (pintype "passive"))
      (node (ref "C2") (pin "1") (pintype "passive"))
      (node (ref "C5") (pin "2") (pintype "passive"))
      (node (ref "C6") (pin "2") (pintype "passive"))
      (node (ref "C8") (pin "B") (pinfunction "B_B") (pintype "passive"))
      (node (ref "C9") (pin "2") (pintype "passive"))
      (node (ref "IR_LED1") (pin "1") (pintype "passive"))
      (node (ref "IR_LED10") (pin "1") (pintype "passive"))
      (node (ref "IR_LED11") (pin "1") (pintype "passive"))
      (node (ref "IR_LED12") (pin "1") (pintype "passive"))
      (node (ref "IR_LED13") (pin "1") (pintype "passive"))
      (node (ref "IR_LED14") (pin "1") (pintype "passive"))
      (node (ref "IR_LED15") (pin "1") (pintype "passive"))
      (node (ref "IR_LED2") (pin "1") (pintype "passive"))
      (node (ref "IR_LED3") (pin "1") (pintype "passive"))
      (node (ref "IR_LED4") (pin "1") (pintype "passive"))
      (node (ref "IR_LED5") (pin "1") (pintype "passive"))
      (node (ref "IR_LED6") (pin "1") (pintype "passive"))
      (node (ref "IR_LED7") (pin "1") (pintype "passive"))
      (node (ref "IR_LED8") (pin "1") (pintype "passive"))
      (node (ref "IR_LED9") (pin "1") (pintype "passive"))
      (node (ref "L1") (pin "1") (pinfunction "B_1") (pintype "passive"))
      (node (ref "R21") (pin "2") (pinfunction "B_2") (pintype "passive"))
      (node (ref "R6") (pin "2") (pinfunction "B_2") (pintype "passive"))
      (node (ref "RGB_LED1") (pin "2") (pinfunction "anode_2") (pintype "passive"))
      (node (ref "cs1") (pin "B") (pinfunction "B_B") (pintype "passive"))
      (node (ref "opamp1") (pin "4") (pinfunction "Vdd_4") (pintype "passive"))
      (node (ref "p7") (pin "4") (pinfunction "PWR_4") (pintype "passive"))
      (node (ref "photo_diode1") (pin "2") (pintype "passive"))
      (node (ref "photo_diode2") (pin "2") (pintype "passive"))
      (node (ref "photo_diode3") (pin "2") (pintype "passive"))
      (node (ref "regulator1") (pin "5") (pinfunction "out_5") (pintype "passive"))
    )
    (net (code "83") (name "unconnected-(*1-Pad21)") (class "Default")
      (node (ref "*1") (pin "21") (pinfunction "21_21") (pintype "passive"))
    )
    (net (code "84") (name "unconnected-(P1-Pad0)") (class "Default")
      (node (ref "P1") (pin "0") (pinfunction "0_0") (pintype "passive"))
    )
    (net (code "85") (name "unconnected-(P2-Pad0)") (class "Default")
      (node (ref "P2") (pin "0") (pinfunction "0_0") (pintype "passive"))
    )
    (net (code "86") (name "unconnected-(P3-Pad0)") (class "Default")
      (node (ref "P3") (pin "0") (pinfunction "0_0") (pintype "passive"))
    )
    (net (code "87") (name "unconnected-(P4-Pad0)") (class "Default")
      (node (ref "P4") (pin "0") (pinfunction "0_0") (pintype "passive"))
    )
    (net (code "88") (name "unconnected-(P5-Pad0)") (class "Default")
      (node (ref "P5") (pin "0") (pinfunction "0_0") (pintype "passive"))
    )
    (net (code "89") (name "unconnected-(P6-Pad0)") (class "Default")
      (node (ref "P6") (pin "0") (pinfunction "0_0") (pintype "passive"))
    )
    (net (code "90") (name "unconnected-(P8-Pad0)") (class "Default")
      (node (ref "P8") (pin "0") (pinfunction "0_0") (pintype "passive"))
    )
    (net (code "91") (name "unconnected-(P9-Pad0)") (class "Default")
      (node (ref "P9") (pin "0") (pinfunction "0_0") (pintype "passive"))
    )
    (net (code "92") (name "unconnected-(P10-Pad0)") (class "Default")
      (node (ref "P10") (pin "0") (pinfunction "0_0") (pintype "passive"))
    )
    (net (code "93") (name "unconnected-(P11-Pad0)") (class "Default")
      (node (ref "P11") (pin "0") (pinfunction "0_0") (pintype "passive"))
    )
    (net (code "94") (name "unconnected-(P12-Pad0)") (class "Default")
      (node (ref "P12") (pin "0") (pinfunction "0_0") (pintype "passive"))
    )
    (net (code "95") (name "unconnected-(P13-Pad0)") (class "Default")
      (node (ref "P13") (pin "0") (pinfunction "0_0") (pintype "passive"))
    )
    (net (code "96") (name "unconnected-(P14-Pad0)") (class "Default")
      (node (ref "P14") (pin "0") (pinfunction "0_0") (pintype "passive"))
    )
    (net (code "97") (name "unconnected-(P15-Pad0)") (class "Default")
      (node (ref "P15") (pin "0") (pinfunction "0_0") (pintype "passive"))
    )
    (net (code "98") (name "unconnected-(P16-Pad0)") (class "Default")
      (node (ref "P16") (pin "0") (pinfunction "0_0") (pintype "passive"))
    )
    (net (code "99") (name "unconnected-(RGB_LED1-blue-Pad3)") (class "Default")
      (node (ref "RGB_LED1") (pin "3") (pinfunction "blue_3") (pintype "passive"))
    )
    (net (code "100") (name "unconnected-(RGB_LED1-green-Pad4)") (class "Default")
      (node (ref "RGB_LED1") (pin "4") (pinfunction "green_4") (pintype "passive"))
    )
    (net (code "101") (name "unconnected-(leg1-out-Pad1)") (class "Default")
      (node (ref "leg1") (pin "1") (pinfunction "out_1") (pintype "passive"))
    )
    (net (code "102") (name "unconnected-(leg2-out-Pad1)") (class "Default")
      (node (ref "leg2") (pin "1") (pinfunction "out_1") (pintype "passive"))
    )
    (net (code "103") (name "unconnected-(leg3-out-Pad1)") (class "Default")
      (node (ref "leg3") (pin "1") (pinfunction "out_1") (pintype "passive"))
    )
    (net (code "104") (name "unconnected-(leg4-out-Pad1)") (class "Default")
      (node (ref "leg4") (pin "1") (pinfunction "out_1") (pintype "passive"))
    )
    (net (code "105") (name "unconnected-(leg5-out-Pad1)") (class "Default")
      (node (ref "leg5") (pin "1") (pinfunction "out_1") (pintype "passive"))
    )
    (net (code "106") (name "unconnected-(leg6-out-Pad1)") (class "Default")
      (node (ref "leg6") (pin "1") (pinfunction "out_1") (pintype "passive"))
    )
    (net (code "107") (name "unconnected-(leg7-out-Pad1)") (class "Default")
      (node (ref "leg7") (pin "1") (pinfunction "out_1") (pintype "passive"))
    )
    (net (code "108") (name "unconnected-(regulator1-nr{slash}fb-Pad4)") (class "Default")
      (node (ref "regulator1") (pin "4") (pinfunction "nr/fb_4") (pintype "passive"))
    )
  )
)
